# DACs.net
KiCad netlist of a schematic drawn in Altium Designer
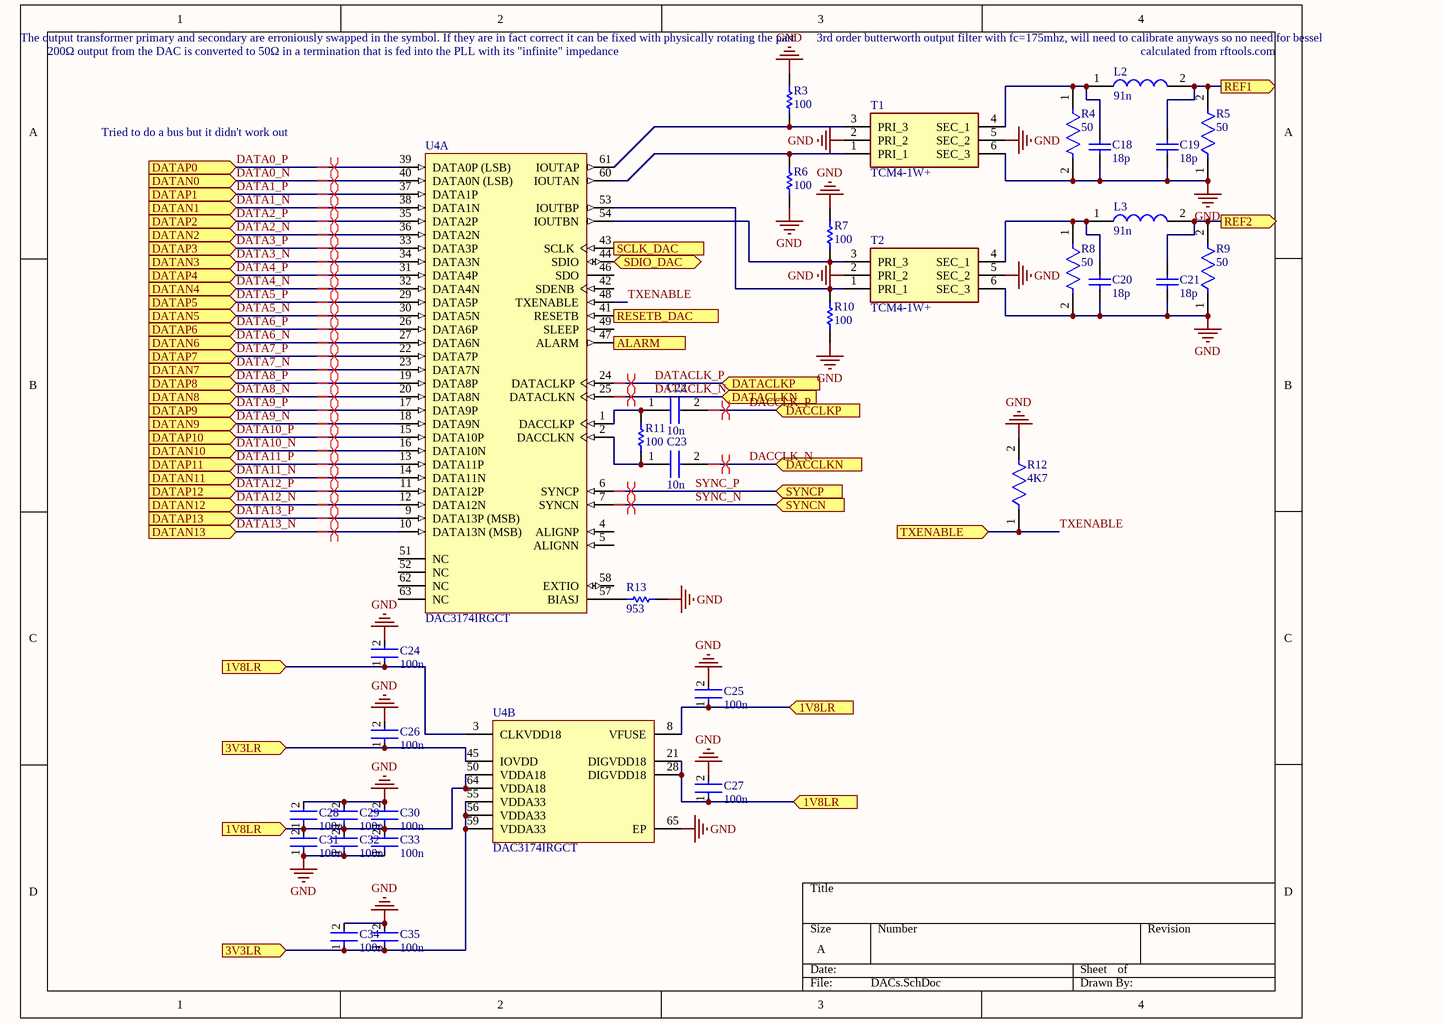
[diagram p0: DACs.SchDoc]

(export (version "E")
  (design (tool "Eeschema 10.0.6"))
  (components
    (comp (ref "C18")
      (value "18p")
      (footprint "CAPC1006X50X20LL10T10")
      (fields
        (field (name "MANUFACTURER") "AVX Interconnect / Elco")
        (field (name "PART NUMBER") "04023K180FBSTR")
      )
      (libsource (lib "Altium Content Vault") (part "CAP"))
    )
    (comp (ref "C19")
      (value "18p")
      (footprint "CAPC1006X50X20LL10T10")
      (fields
        (field (name "MANUFACTURER") "AVX Interconnect / Elco")
        (field (name "PART NUMBER") "04023K180FBSTR")
      )
      (libsource (lib "Altium Content Vault") (part "CAP"))
    )
    (comp (ref "C20")
      (value "18p")
      (footprint "CAPC1006X50X20LL10T10")
      (fields
        (field (name "MANUFACTURER") "AVX Interconnect / Elco")
        (field (name "PART NUMBER") "04023K180FBSTR")
      )
      (libsource (lib "Altium Content Vault") (part "CAP"))
    )
    (comp (ref "C21")
      (value "18p")
      (footprint "CAPC1006X50X20LL10T10")
      (fields
        (field (name "MANUFACTURER") "AVX Interconnect / Elco")
        (field (name "PART NUMBER") "04023K180FBSTR")
      )
      (libsource (lib "Altium Content Vault") (part "CAP"))
    )
    (comp (ref "C22")
      (value "10n")
      (footprint "SamacSys:CAPC1005X61N")
      (description "Capacitor")
      (fields
        (field (name "MANUFACTURER_PART_NUMBER") "520L103KT16T")
        (field (name "MOUSER PART NUMBER") "581-520L103KT16T")
      )
      (libsource (lib "*") (part "520L103KT16T"))
    )
    (comp (ref "C23")
      (value "10n")
      (footprint "SamacSys:CAPC1005X61N")
      (description "Capacitor")
      (fields
        (field (name "MANUFACTURER_PART_NUMBER") "520L103KT16T")
        (field (name "MOUSER PART NUMBER") "581-520L103KT16T")
      )
      (libsource (lib "*") (part "520L103KT16T"))
    )
    (comp (ref "C24")
      (value "100n")
      (footprint "FP-GRM155-0_05-IPC_C")
      (description "Chip Multilayer Ceramic Capacitors for General Purpose, 0402, 0.10uF, X5R, 15%, 10%, 100V")
      (fields (field (name "TOLERANCE") "10%"))
      (libsource (lib "Altium Content Vault") (part "02cd4be3c70576c341d710602a673aa"))
    )
    (comp (ref "C25")
      (value "100n")
      (footprint "FP-GRM155-0_05-IPC_C")
      (description "Chip Multilayer Ceramic Capacitors for General Purpose, 0402, 0.10uF, X5R, 15%, 10%, 100V")
      (fields (field (name "TOLERANCE") "10%"))
      (libsource (lib "Altium Content Vault") (part "02cd4be3c70576c341d710602a673aa"))
    )
    (comp (ref "C26")
      (value "100n")
      (footprint "FP-GRM155-0_05-IPC_C")
      (description "Chip Multilayer Ceramic Capacitors for General Purpose, 0402, 0.10uF, X5R, 15%, 10%, 100V")
      (fields (field (name "TOLERANCE") "10%"))
      (libsource (lib "Altium Content Vault") (part "02cd4be3c70576c341d710602a673aa"))
    )
    (comp (ref "C27")
      (value "100n")
      (footprint "FP-GRM155-0_05-IPC_C")
      (description "Chip Multilayer Ceramic Capacitors for General Purpose, 0402, 0.10uF, X5R, 15%, 10%, 100V")
      (fields (field (name "TOLERANCE") "10%"))
      (libsource (lib "Altium Content Vault") (part "02cd4be3c70576c341d710602a673aa"))
    )
    (comp (ref "C28")
      (value "100n")
      (footprint "FP-GRM155-0_05-IPC_C")
      (description "Chip Multilayer Ceramic Capacitors for General Purpose, 0402, 0.10uF, X5R, 15%, 10%, 100V")
      (fields (field (name "TOLERANCE") "10%"))
      (libsource (lib "Altium Content Vault") (part "02cd4be3c70576c341d710602a673aa"))
    )
    (comp (ref "C29")
      (value "100n")
      (footprint "FP-GRM155-0_05-IPC_C")
      (description "Chip Multilayer Ceramic Capacitors for General Purpose, 0402, 0.10uF, X5R, 15%, 10%, 100V")
      (fields (field (name "TOLERANCE") "10%"))
      (libsource (lib "Altium Content Vault") (part "02cd4be3c70576c341d710602a673aa"))
    )
    (comp (ref "C30")
      (value "100n")
      (footprint "FP-GRM155-0_05-IPC_C")
      (description "Chip Multilayer Ceramic Capacitors for General Purpose, 0402, 0.10uF, X5R, 15%, 10%, 100V")
      (fields (field (name "TOLERANCE") "10%"))
      (libsource (lib "Altium Content Vault") (part "02cd4be3c70576c341d710602a673aa"))
    )
    (comp (ref "C31")
      (value "100n")
      (footprint "FP-GRM155-0_05-IPC_C")
      (description "Chip Multilayer Ceramic Capacitors for General Purpose, 0402, 0.10uF, X5R, 15%, 10%, 100V")
      (fields (field (name "TOLERANCE") "10%"))
      (libsource (lib "Altium Content Vault") (part "02cd4be3c70576c341d710602a673aa"))
    )
    (comp (ref "C32")
      (value "100n")
      (footprint "FP-GRM155-0_05-IPC_C")
      (description "Chip Multilayer Ceramic Capacitors for General Purpose, 0402, 0.10uF, X5R, 15%, 10%, 100V")
      (fields (field (name "TOLERANCE") "10%"))
      (libsource (lib "Altium Content Vault") (part "02cd4be3c70576c341d710602a673aa"))
    )
    (comp (ref "C33")
      (value "100n")
      (footprint "FP-GRM155-0_05-IPC_C")
      (description "Chip Multilayer Ceramic Capacitors for General Purpose, 0402, 0.10uF, X5R, 15%, 10%, 100V")
      (fields (field (name "TOLERANCE") "10%"))
      (libsource (lib "Altium Content Vault") (part "02cd4be3c70576c341d710602a673aa"))
    )
    (comp (ref "C34")
      (value "100n")
      (footprint "FP-GRM155-0_05-IPC_C")
      (description "Chip Multilayer Ceramic Capacitors for General Purpose, 0402, 0.10uF, X5R, 15%, 10%, 100V")
      (fields (field (name "TOLERANCE") "10%"))
      (libsource (lib "Altium Content Vault") (part "02cd4be3c70576c341d710602a673aa"))
    )
    (comp (ref "C35")
      (value "100n")
      (footprint "FP-GRM155-0_05-IPC_C")
      (description "Chip Multilayer Ceramic Capacitors for General Purpose, 0402, 0.10uF, X5R, 15%, 10%, 100V")
      (fields (field (name "TOLERANCE") "10%"))
      (libsource (lib "Altium Content Vault") (part "02cd4be3c70576c341d710602a673aa"))
    )
    (comp (ref "L2")
      (value "91n")
      (footprint "SamacSys:INDC1006X65N")
      (description "Inductor")
      (fields
        (field (name "MANUFACTURER_PART_NUMBER") "MLJ1005HXG91NJTD0B")
        (field (name "MOUSER PART NUMBER") "810-MLJ1005HXG91NJTD")
      )
      (libsource (lib "*") (part "MLJ1005HXG91NJTD0B"))
    )
    (comp (ref "L3")
      (value "91n")
      (footprint "SamacSys:INDC1006X65N")
      (description "Inductor")
      (fields
        (field (name "MANUFACTURER_PART_NUMBER") "MLJ1005HXG91NJTD0B")
        (field (name "MOUSER PART NUMBER") "810-MLJ1005HXG91NJTD")
      )
      (libsource (lib "*") (part "MLJ1005HXG91NJTD0B"))
    )
    (comp (ref "R3")
      (value "100")
      (footprint "RESC1005X40X25LL05T05")
      (description "Chip Resistor, 100 Ohm, +/- 1%, 100 mW, -55 to 155 degC, 0402 (1005 Metric), RoHS, Tape and Reel")
      (fields (field (name "MANUFACTURER") "Basic Passives") (field (name "TOLERANCE") "1%"))
      (libsource (lib "Altium Content Vault") (part "RES-2"))
    )
    (comp (ref "R4")
      (value "50")
      (footprint "FP-RC0402-0_4-MFG")
      (fields (field (name "TOLERANCE") "5%"))
      (libsource (lib "Altium Content Vault") (part "1029c3af85768c4190bb7ad29bc67b5"))
    )
    (comp (ref "R5")
      (value "50")
      (footprint "FP-RC0402-0_4-MFG")
      (fields (field (name "TOLERANCE") "5%"))
      (libsource (lib "Altium Content Vault") (part "1029c3af85768c4190bb7ad29bc67b5"))
    )
    (comp (ref "R6")
      (value "100")
      (footprint "RESC1005X40X25LL05T05")
      (description "Chip Resistor, 100 Ohm, +/- 1%, 100 mW, -55 to 155 degC, 0402 (1005 Metric), RoHS, Tape and Reel")
      (fields (field (name "MANUFACTURER") "Basic Passives") (field (name "TOLERANCE") "1%"))
      (libsource (lib "Altium Content Vault") (part "RES-2"))
    )
    (comp (ref "R7")
      (value "100")
      (footprint "RESC1005X40X25LL05T05")
      (description "Chip Resistor, 100 Ohm, +/- 1%, 100 mW, -55 to 155 degC, 0402 (1005 Metric), RoHS, Tape and Reel")
      (fields (field (name "MANUFACTURER") "Basic Passives") (field (name "TOLERANCE") "1%"))
      (libsource (lib "Altium Content Vault") (part "RES-2"))
    )
    (comp (ref "R8")
      (value "50")
      (footprint "FP-RC0402-0_4-MFG")
      (fields (field (name "TOLERANCE") "5%"))
      (libsource (lib "Altium Content Vault") (part "1029c3af85768c4190bb7ad29bc67b5"))
    )
    (comp (ref "R9")
      (value "50")
      (footprint "FP-RC0402-0_4-MFG")
      (fields (field (name "TOLERANCE") "5%"))
      (libsource (lib "Altium Content Vault") (part "1029c3af85768c4190bb7ad29bc67b5"))
    )
    (comp (ref "R10")
      (value "100")
      (footprint "RESC1005X40X25LL05T05")
      (description "Chip Resistor, 100 Ohm, +/- 1%, 100 mW, -55 to 155 degC, 0402 (1005 Metric), RoHS, Tape and Reel")
      (fields (field (name "MANUFACTURER") "Basic Passives") (field (name "TOLERANCE") "1%"))
      (libsource (lib "Altium Content Vault") (part "RES-2"))
    )
    (comp (ref "R11")
      (value "100")
      (footprint "RESC1005X40X25LL05T05")
      (description "Chip Resistor, 100 Ohm, +/- 1%, 100 mW, -55 to 155 degC, 0402 (1005 Metric), RoHS, Tape and Reel")
      (fields (field (name "MANUFACTURER") "Basic Passives") (field (name "TOLERANCE") "1%"))
      (libsource (lib "Altium Content Vault") (part "RES-2"))
    )
    (comp (ref "R12")
      (value "4K7")
      (footprint "FP-RT0402-MFG")
      (description "RES 4.70K OHM 1/16W 1% SMD 0402")
      (fields
        (field (name "MANUFACTURER PART NUMBER") "RT0402FRE074K7L")
        (field (name "MANUFACTURER") "Yageo")
      )
      (libsource (lib "Altium Content Vault") (part "1029c3af85768c4190bb7ad29bc67b5"))
    )
    (comp (ref "R13")
      (value "953")
      (footprint "RESC1005X40X25NL10T10")
      (fields (field (name "MANUFACTURER") "KOA Speer") (field (name "PART NUMBER") "RK73H1ETTP9530F"))
      (libsource (lib "Altium Content Vault") (part "RES"))
    )
    (comp (ref "T1")
      (value "TCM4-1W+")
      (footprint "SamacSys:TCM41W")
      (description "Transformer")
      (fields (field (name "MOUSER PART NUMBER") "139-TCM4-1W"))
      (libsource (lib "*") (part "TCM4-1W+"))
    )
    (comp (ref "T2")
      (value "TCM4-1W+")
      (footprint "SamacSys:TCM41W")
      (description "Transformer")
      (fields (field (name "MOUSER PART NUMBER") "139-TCM4-1W"))
      (libsource (lib "*") (part "TCM4-1W+"))
    )
    (comp (ref "U4")
      (value "DAC3174IRGCT")
      (footprint "TI-RGC64-7400X7400TP_V")
      (fields (field (name "MANUFACTURER") "Texas Instruments"))
      (libsource (lib "Altium Content Vault") (part "TI-DAC3174-RGC64"))
    )
  )
  (nets
    (net (code "1") (name "/1V8LR") (class "Default")
      (node (ref "C24") (pin "1") (pinfunction "1_1") (pintype "passive"))
      (node (ref "C25") (pin "1") (pinfunction "1_1") (pintype "passive"))
      (node (ref "C27") (pin "1") (pinfunction "1_1") (pintype "passive"))
      (node (ref "C28") (pin "1") (pinfunction "1_1") (pintype "passive"))
      (node (ref "C29") (pin "1") (pinfunction "1_1") (pintype "passive"))
      (node (ref "C30") (pin "1") (pinfunction "1_1") (pintype "passive"))
      (node (ref "C31") (pin "2") (pinfunction "2_2") (pintype "passive"))
      (node (ref "C32") (pin "2") (pinfunction "2_2") (pintype "passive"))
      (node (ref "C33") (pin "2") (pinfunction "2_2") (pintype "passive"))
      (node (ref "U4") (pin "21") (pinfunction "DIGVDD18_21") (pintype "power_in"))
      (node (ref "U4") (pin "28") (pinfunction "DIGVDD18_28") (pintype "power_in"))
      (node (ref "U4") (pin "3") (pinfunction "CLKVDD18_3") (pintype "power_in"))
      (node (ref "U4") (pin "50") (pinfunction "VDDA18_50") (pintype "power_in"))
      (node (ref "U4") (pin "64") (pinfunction "VDDA18_64") (pintype "power_in"))
      (node (ref "U4") (pin "8") (pinfunction "VFUSE_8") (pintype "power_in"))
    )
    (net (code "2") (name "/3V3LR") (class "Default")
      (node (ref "C26") (pin "1") (pinfunction "1_1") (pintype "passive"))
      (node (ref "C34") (pin "1") (pinfunction "1_1") (pintype "passive"))
      (node (ref "C35") (pin "1") (pinfunction "1_1") (pintype "passive"))
      (node (ref "U4") (pin "45") (pinfunction "IOVDD_45") (pintype "power_in"))
      (node (ref "U4") (pin "55") (pinfunction "VDDA33_55") (pintype "power_in"))
      (node (ref "U4") (pin "56") (pinfunction "VDDA33_56") (pintype "power_in"))
      (node (ref "U4") (pin "59") (pinfunction "VDDA33_59") (pintype "power_in"))
    )
    (net (code "3") (name "/ALARM") (class "Default")
      (node (ref "U4") (pin "47") (pinfunction "ALARM_47") (pintype "output"))
    )
    (net (code "4") (name "/DACCLK_N") (class "Default")
      (node (ref "C23") (pin "2") (pinfunction "2_2") (pintype "passive"))
    )
    (net (code "5") (name "/DACCLK_P") (class "Default")
      (node (ref "C22") (pin "2") (pinfunction "2_2") (pintype "passive"))
    )
    (net (code "6") (name "/DATA0_N") (class "Default")
      (node (ref "U4") (pin "40") (pinfunction "DATA0N_(LSB)_40") (pintype "input"))
    )
    (net (code "7") (name "/DATA0_P") (class "Default")
      (node (ref "U4") (pin "39") (pinfunction "DATA0P_(LSB)_39") (pintype "input"))
    )
    (net (code "8") (name "/DATA1_N") (class "Default")
      (node (ref "U4") (pin "38") (pinfunction "DATA1N_38") (pintype "input"))
    )
    (net (code "9") (name "/DATA1_P") (class "Default")
      (node (ref "U4") (pin "37") (pinfunction "DATA1P_37") (pintype "input"))
    )
    (net (code "10") (name "/DATA2_N") (class "Default")
      (node (ref "U4") (pin "36") (pinfunction "DATA2N_36") (pintype "input"))
    )
    (net (code "11") (name "/DATA2_P") (class "Default")
      (node (ref "U4") (pin "35") (pinfunction "DATA2P_35") (pintype "input"))
    )
    (net (code "12") (name "/DATA3_N") (class "Default")
      (node (ref "U4") (pin "34") (pinfunction "DATA3N_34") (pintype "input"))
    )
    (net (code "13") (name "/DATA3_P") (class "Default")
      (node (ref "U4") (pin "33") (pinfunction "DATA3P_33") (pintype "input"))
    )
    (net (code "14") (name "/DATA4_N") (class "Default")
      (node (ref "U4") (pin "32") (pinfunction "DATA4N_32") (pintype "input"))
    )
    (net (code "15") (name "/DATA4_P") (class "Default")
      (node (ref "U4") (pin "31") (pinfunction "DATA4P_31") (pintype "input"))
    )
    (net (code "16") (name "/DATA5_N") (class "Default")
      (node (ref "U4") (pin "30") (pinfunction "DATA5N_30") (pintype "input"))
    )
    (net (code "17") (name "/DATA5_P") (class "Default")
      (node (ref "U4") (pin "29") (pinfunction "DATA5P_29") (pintype "input"))
    )
    (net (code "18") (name "/DATA6_N") (class "Default")
      (node (ref "U4") (pin "27") (pinfunction "DATA6N_27") (pintype "input"))
    )
    (net (code "19") (name "/DATA6_P") (class "Default")
      (node (ref "U4") (pin "26") (pinfunction "DATA6P_26") (pintype "input"))
    )
    (net (code "20") (name "/DATA7_N") (class "Default")
      (node (ref "U4") (pin "23") (pinfunction "DATA7N_23") (pintype "input"))
    )
    (net (code "21") (name "/DATA7_P") (class "Default")
      (node (ref "U4") (pin "22") (pinfunction "DATA7P_22") (pintype "input"))
    )
    (net (code "22") (name "/DATA8_N") (class "Default")
      (node (ref "U4") (pin "20") (pinfunction "DATA8N_20") (pintype "input"))
    )
    (net (code "23") (name "/DATA8_P") (class "Default")
      (node (ref "U4") (pin "19") (pinfunction "DATA8P_19") (pintype "input"))
    )
    (net (code "24") (name "/DATA9_N") (class "Default")
      (node (ref "U4") (pin "18") (pinfunction "DATA9N_18") (pintype "input"))
    )
    (net (code "25") (name "/DATA9_P") (class "Default")
      (node (ref "U4") (pin "17") (pinfunction "DATA9P_17") (pintype "input"))
    )
    (net (code "26") (name "/DATA10_N") (class "Default")
      (node (ref "U4") (pin "16") (pinfunction "DATA10N_16") (pintype "input"))
    )
    (net (code "27") (name "/DATA10_P") (class "Default")
      (node (ref "U4") (pin "15") (pinfunction "DATA10P_15") (pintype "input"))
    )
    (net (code "28") (name "/DATA11_N") (class "Default")
      (node (ref "U4") (pin "14") (pinfunction "DATA11N_14") (pintype "input"))
    )
    (net (code "29") (name "/DATA11_P") (class "Default")
      (node (ref "U4") (pin "13") (pinfunction "DATA11P_13") (pintype "input"))
    )
    (net (code "30") (name "/DATA12_N") (class "Default")
      (node (ref "U4") (pin "12") (pinfunction "DATA12N_12") (pintype "input"))
    )
    (net (code "31") (name "/DATA12_P") (class "Default")
      (node (ref "U4") (pin "11") (pinfunction "DATA12P_11") (pintype "input"))
    )
    (net (code "32") (name "/DATA13_N") (class "Default")
      (node (ref "U4") (pin "10") (pinfunction "DATA13N_(MSB)_10") (pintype "input"))
    )
    (net (code "33") (name "/DATA13_P") (class "Default")
      (node (ref "U4") (pin "9") (pinfunction "DATA13P_(MSB)_9") (pintype "input"))
    )
    (net (code "34") (name "/DATACLK_N") (class "Default")
      (node (ref "U4") (pin "25") (pinfunction "DATACLKN_25") (pintype "input"))
    )
    (net (code "35") (name "/DATACLK_P") (class "Default")
      (node (ref "U4") (pin "24") (pinfunction "DATACLKP_24") (pintype "input"))
    )
    (net (code "36") (name "/REF1") (class "Default")
      (node (ref "C19") (pin "2") (pinfunction "2_2") (pintype "passive"))
      (node (ref "L2") (pin "2") (pinfunction "2_2") (pintype "passive"))
      (node (ref "R5") (pin "2") (pinfunction "2_2") (pintype "passive"))
    )
    (net (code "37") (name "/REF2") (class "Default")
      (node (ref "C21") (pin "2") (pinfunction "2_2") (pintype "passive"))
      (node (ref "L3") (pin "2") (pinfunction "2_2") (pintype "passive"))
      (node (ref "R9") (pin "2") (pinfunction "2_2") (pintype "passive"))
    )
    (net (code "38") (name "/RESETB_DAC") (class "Default")
      (node (ref "U4") (pin "41") (pinfunction "RESETB_41") (pintype "input"))
    )
    (net (code "39") (name "/SCLK_DAC") (class "Default")
      (node (ref "U4") (pin "43") (pinfunction "SCLK_43") (pintype "input"))
    )
    (net (code "40") (name "/SDIO_DAC") (class "Default")
      (node (ref "U4") (pin "44") (pinfunction "SDIO_44") (pintype "bidirectional"))
    )
    (net (code "41") (name "/SYNC_N") (class "Default")
      (node (ref "U4") (pin "7") (pinfunction "SYNCN_7") (pintype "input"))
    )
    (net (code "42") (name "/SYNC_P") (class "Default")
      (node (ref "U4") (pin "6") (pinfunction "SYNCP_6") (pintype "input"))
    )
    (net (code "43") (name "/TXENABLE") (class "Default")
      (node (ref "R12") (pin "1") (pinfunction "1_1") (pintype "passive"))
      (node (ref "U4") (pin "48") (pinfunction "TXENABLE_48") (pintype "input"))
    )
    (net (code "44") (name "GND") (class "Default")
      (node (ref "C18") (pin "1") (pinfunction "1_1") (pintype "passive"))
      (node (ref "C19") (pin "1") (pinfunction "1_1") (pintype "passive"))
      (node (ref "C20") (pin "1") (pinfunction "1_1") (pintype "passive"))
      (node (ref "C21") (pin "1") (pinfunction "1_1") (pintype "passive"))
      (node (ref "C24") (pin "2") (pinfunction "2_2") (pintype "passive"))
      (node (ref "C25") (pin "2") (pinfunction "2_2") (pintype "passive"))
      (node (ref "C26") (pin "2") (pinfunction "2_2") (pintype "passive"))
      (node (ref "C27") (pin "2") (pinfunction "2_2") (pintype "passive"))
      (node (ref "C28") (pin "2") (pinfunction "2_2") (pintype "passive"))
      (node (ref "C29") (pin "2") (pinfunction "2_2") (pintype "passive"))
      (node (ref "C30") (pin "2") (pinfunction "2_2") (pintype "passive"))
      (node (ref "C31") (pin "1") (pinfunction "1_1") (pintype "passive"))
      (node (ref "C32") (pin "1") (pinfunction "1_1") (pintype "passive"))
      (node (ref "C33") (pin "1") (pinfunction "1_1") (pintype "passive"))
      (node (ref "C34") (pin "2") (pinfunction "2_2") (pintype "passive"))
      (node (ref "C35") (pin "2") (pinfunction "2_2") (pintype "passive"))
      (node (ref "R10") (pin "1") (pinfunction "1_1") (pintype "passive"))
      (node (ref "R12") (pin "2") (pinfunction "2_2") (pintype "passive"))
      (node (ref "R13") (pin "2") (pinfunction "2_2") (pintype "passive"))
      (node (ref "R3") (pin "2") (pinfunction "2_2") (pintype "passive"))
      (node (ref "R4") (pin "2") (pinfunction "2_2") (pintype "passive"))
      (node (ref "R5") (pin "1") (pinfunction "1_1") (pintype "passive"))
      (node (ref "R6") (pin "1") (pinfunction "1_1") (pintype "passive"))
      (node (ref "R7") (pin "2") (pinfunction "2_2") (pintype "passive"))
      (node (ref "R8") (pin "2") (pinfunction "2_2") (pintype "passive"))
      (node (ref "R9") (pin "1") (pinfunction "1_1") (pintype "passive"))
      (node (ref "T1") (pin "2") (pinfunction "PRI_2_2") (pintype "passive"))
      (node (ref "T1") (pin "5") (pinfunction "SEC_2_5") (pintype "passive"))
      (node (ref "T1") (pin "6") (pinfunction "SEC_3_6") (pintype "passive"))
      (node (ref "T2") (pin "2") (pinfunction "PRI_2_2") (pintype "passive"))
      (node (ref "T2") (pin "5") (pinfunction "SEC_2_5") (pintype "passive"))
      (node (ref "T2") (pin "6") (pinfunction "SEC_3_6") (pintype "passive"))
      (node (ref "U4") (pin "65") (pinfunction "EP_65") (pintype "power_in"))
    )
    (net (code "45") (name "Net-(T1-PRI_1)") (class "Default")
      (node (ref "R6") (pin "2") (pinfunction "2_2") (pintype "passive"))
      (node (ref "T1") (pin "1") (pinfunction "PRI_1_1") (pintype "passive"))
      (node (ref "U4") (pin "60") (pinfunction "IOUTAN_60") (pintype "output"))
    )
    (net (code "46") (name "Net-(T1-PRI_3)") (class "Default")
      (node (ref "R3") (pin "1") (pinfunction "1_1") (pintype "passive"))
      (node (ref "T1") (pin "3") (pinfunction "PRI_3_3") (pintype "passive"))
      (node (ref "U4") (pin "61") (pinfunction "IOUTAP_61") (pintype "output"))
    )
    (net (code "47") (name "Net-(T1-SEC_1)") (class "Default")
      (node (ref "C18") (pin "2") (pinfunction "2_2") (pintype "passive"))
      (node (ref "L2") (pin "1") (pinfunction "1_1") (pintype "passive"))
      (node (ref "R4") (pin "1") (pinfunction "1_1") (pintype "passive"))
      (node (ref "T1") (pin "4") (pinfunction "SEC_1_4") (pintype "passive"))
    )
    (net (code "48") (name "Net-(T2-PRI_1)") (class "Default")
      (node (ref "R10") (pin "2") (pinfunction "2_2") (pintype "passive"))
      (node (ref "T2") (pin "1") (pinfunction "PRI_1_1") (pintype "passive"))
      (node (ref "U4") (pin "53") (pinfunction "IOUTBP_53") (pintype "output"))
    )
    (net (code "49") (name "Net-(T2-PRI_3)") (class "Default")
      (node (ref "R7") (pin "1") (pinfunction "1_1") (pintype "passive"))
      (node (ref "T2") (pin "3") (pinfunction "PRI_3_3") (pintype "passive"))
      (node (ref "U4") (pin "54") (pinfunction "IOUTBN_54") (pintype "output"))
    )
    (net (code "50") (name "Net-(T2-SEC_1)") (class "Default")
      (node (ref "C20") (pin "2") (pinfunction "2_2") (pintype "passive"))
      (node (ref "L3") (pin "1") (pinfunction "1_1") (pintype "passive"))
      (node (ref "R8") (pin "1") (pinfunction "1_1") (pintype "passive"))
      (node (ref "T2") (pin "4") (pinfunction "SEC_1_4") (pintype "passive"))
    )
    (net (code "51") (name "Net-(U4A-BIASJ)") (class "Default")
      (node (ref "R13") (pin "1") (pinfunction "1_1") (pintype "passive"))
      (node (ref "U4") (pin "57") (pinfunction "BIASJ_57") (pintype "passive"))
    )
    (net (code "52") (name "Net-(U4A-DACCLKN)") (class "Default")
      (node (ref "C23") (pin "1") (pinfunction "1_1") (pintype "passive"))
      (node (ref "R11") (pin "1") (pinfunction "1_1") (pintype "passive"))
      (node (ref "U4") (pin "2") (pinfunction "DACCLKN_2") (pintype "input"))
    )
    (net (code "53") (name "Net-(U4A-DACCLKP)") (class "Default")
      (node (ref "C22") (pin "1") (pinfunction "1_1") (pintype "passive"))
      (node (ref "R11") (pin "2") (pinfunction "2_2") (pintype "passive"))
      (node (ref "U4") (pin "1") (pinfunction "DACCLKP_1") (pintype "input"))
    )
    (net (code "54") (name "unconnected-(U4A-ALIGNN-Pad5)") (class "Default")
      (node (ref "U4") (pin "5") (pinfunction "ALIGNN_5") (pintype "input"))
    )
    (net (code "55") (name "unconnected-(U4A-ALIGNP-Pad4)") (class "Default")
      (node (ref "U4") (pin "4") (pinfunction "ALIGNP_4") (pintype "input"))
    )
    (net (code "56") (name "unconnected-(U4A-EXTIO-Pad58)") (class "Default")
      (node (ref "U4") (pin "58") (pinfunction "EXTIO_58") (pintype "bidirectional"))
    )
    (net (code "57") (name "unconnected-(U4A-NC-Pad51)") (class "Default")
      (node (ref "U4") (pin "51") (pinfunction "NC_51") (pintype "passive"))
    )
    (net (code "58") (name "unconnected-(U4A-NC-Pad52)") (class "Default")
      (node (ref "U4") (pin "52") (pinfunction "NC_52") (pintype "passive"))
    )
    (net (code "59") (name "unconnected-(U4A-NC-Pad62)") (class "Default")
      (node (ref "U4") (pin "62") (pinfunction "NC_62") (pintype "passive"))
    )
    (net (code "60") (name "unconnected-(U4A-NC-Pad63)") (class "Default")
      (node (ref "U4") (pin "63") (pinfunction "NC_63") (pintype "passive"))
    )
    (net (code "61") (name "unconnected-(U4A-SDENB-Pad42)") (class "Default")
      (node (ref "U4") (pin "42") (pinfunction "SDENB_42") (pintype "input"))
    )
    (net (code "62") (name "unconnected-(U4A-SDO-Pad46)") (class "Default")
      (node (ref "U4") (pin "46") (pinfunction "SDO_46") (pintype "tri_state"))
    )
    (net (code "63") (name "unconnected-(U4A-SLEEP-Pad49)") (class "Default")
      (node (ref "U4") (pin "49") (pinfunction "SLEEP_49") (pintype "input"))
    )
  )
)
